# neopixel-controller.net
KiCad netlist of a schematic drawn in EAGLE
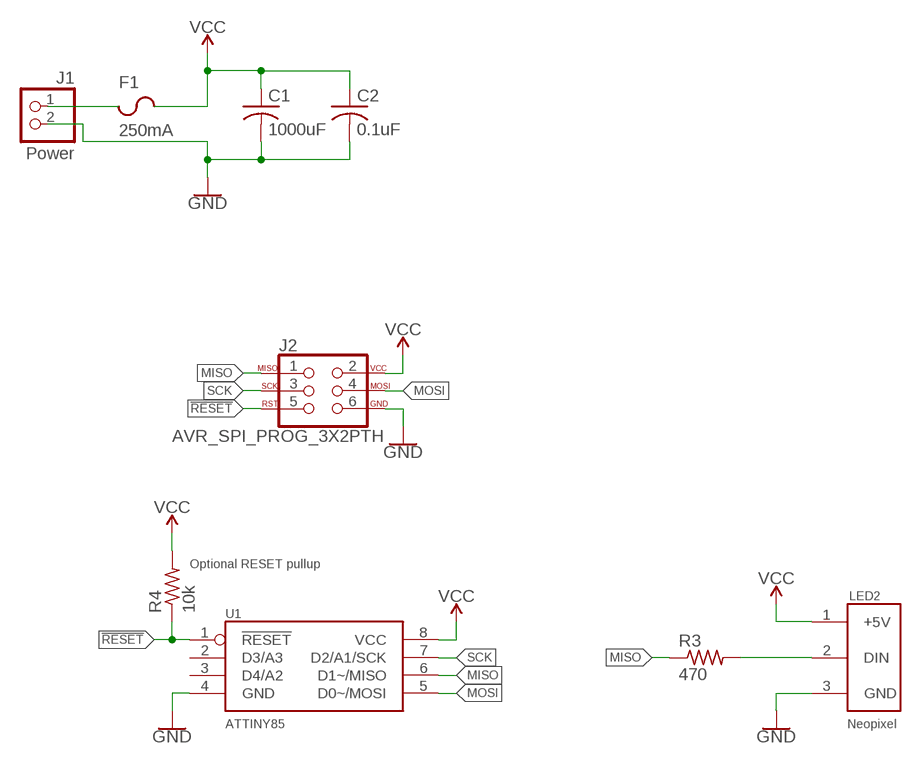
[diagram p0: schematic, sheet 1]

(export (version "E")
  (design (tool "Eeschema 10.0.6"))
  (components
    (comp (ref "C1")
      (value "1000uF")
      (footprint "eagle-import:CAP-3,5-8")
      (libsource (lib "eagle-import") (part "CAPACITOR"))
    )
    (comp (ref "C2")
      (value "0.1uF")
      (footprint "eagle-import:C0805")
      (libsource (lib "eagle-import") (part "C-USC0805"))
    )
    (comp (ref "F1")
      (value "250mA")
      (footprint "eagle-import:F1206")
      (libsource (lib "eagle-import") (part "FUSE"))
    )
    (comp (ref "J1")
      (value "Power")
      (footprint "eagle-import:1X02")
      (libsource (lib "eagle-import") (part "PINHD-1X2"))
    )
    (comp (ref "J2")
      (value "AVR_SPI_PROG_3X2PTH")
      (footprint "eagle-import:2X3")
      (libsource (lib "eagle-import") (part "AVR_SPI_PROG_3X2PTH"))
    )
    (comp (ref "LED2")
      (value "Neopixel")
      (footprint "eagle-import:NEOPIXEL_PINHEAD")
      (libsource (lib "eagle-import") (part "NEOPIXEL0.100_PINHEAD"))
    )
    (comp (ref "R3")
      (value "470")
      (footprint "eagle-import:R0805")
      (libsource (lib "eagle-import") (part "R-US_R0805"))
    )
    (comp (ref "R4")
      (value "10k")
      (footprint "eagle-import:R0805")
      (libsource (lib "eagle-import") (part "R-US_R0805"))
    )
    (comp (ref "U1")
      (value "ATTINY85")
      (footprint "eagle-import:8S2")
      (libsource (lib "eagle-import") (part "ATTINY85"))
    )
  )
  (nets
    (net (code "1") (name "/~{RESET}") (class "Default")
      (node (ref "J2") (pin "5") (pinfunction "5_5") (pintype "passive"))
      (node (ref "R4") (pin "1") (pinfunction "1_1") (pintype "passive"))
      (node (ref "U1") (pin "1") (pinfunction "~{RESET}_1") (pintype "input"))
    )
    (net (code "2") (name "GND") (class "Default")
      (node (ref "C1") (pin "NEGATIVE") (pinfunction "NEGATIVE_NEGATIVE") (pintype "passive"))
      (node (ref "C2") (pin "2") (pinfunction "2_2") (pintype "passive"))
      (node (ref "J1") (pin "2") (pinfunction "2_2") (pintype "passive"))
      (node (ref "J2") (pin "6") (pinfunction "6_6") (pintype "passive"))
      (node (ref "LED2") (pin "3") (pinfunction "GND_3") (pintype "power_in"))
      (node (ref "U1") (pin "4") (pinfunction "GND_4") (pintype "power_in"))
    )
    (net (code "3") (name "MISO") (class "Default")
      (node (ref "J2") (pin "1") (pinfunction "1_1") (pintype "passive"))
      (node (ref "R3") (pin "1") (pinfunction "1_1") (pintype "passive"))
      (node (ref "U1") (pin "6") (pinfunction "D1~{/MISO}_6") (pintype "bidirectional"))
    )
    (net (code "4") (name "MOSI") (class "Default")
      (node (ref "J2") (pin "4") (pinfunction "4_4") (pintype "passive"))
      (node (ref "U1") (pin "5") (pinfunction "D0~{/MOSI}_5") (pintype "bidirectional"))
    )
    (net (code "5") (name "Net-(F1-Pad1)") (class "Default")
      (node (ref "F1") (pin "1") (pinfunction "1_1") (pintype "bidirectional"))
      (node (ref "J1") (pin "1") (pinfunction "1_1") (pintype "passive"))
    )
    (net (code "6") (name "Net-(LED2-DIN)") (class "Default")
      (node (ref "LED2") (pin "2") (pinfunction "DIN_2") (pintype "input"))
      (node (ref "R3") (pin "2") (pinfunction "2_2") (pintype "passive"))
    )
    (net (code "7") (name "SCK") (class "Default")
      (node (ref "J2") (pin "3") (pinfunction "3_3") (pintype "passive"))
      (node (ref "U1") (pin "7") (pinfunction "D2/A1/SCK_7") (pintype "bidirectional"))
    )
    (net (code "8") (name "VCC") (class "Default")
      (node (ref "C1") (pin "POSITIVE") (pinfunction "POSITIVE_POSITIVE") (pintype "passive"))
      (node (ref "C2") (pin "1") (pinfunction "1_1") (pintype "passive"))
      (node (ref "F1") (pin "2") (pinfunction "2_2") (pintype "bidirectional"))
      (node (ref "J2") (pin "2") (pinfunction "2_2") (pintype "passive"))
      (node (ref "LED2") (pin "1") (pinfunction "+5V_1") (pintype "power_in"))
      (node (ref "R4") (pin "2") (pinfunction "2_2") (pintype "passive"))
      (node (ref "U1") (pin "8") (pinfunction "VCC_8") (pintype "power_in"))
    )
    (net (code "9") (name "unconnected-(U1-D3{slash}A3-Pad2)") (class "Default")
      (node (ref "U1") (pin "2") (pinfunction "D3/A3_2") (pintype "bidirectional"))
    )
    (net (code "10") (name "unconnected-(U1-D4{slash}A2-Pad3)") (class "Default")
      (node (ref "U1") (pin "3") (pinfunction "D4/A2_3") (pintype "bidirectional"))
    )
  )
)
